# CHIP.net
KiCad netlist of a schematic drawn in Altium Designer
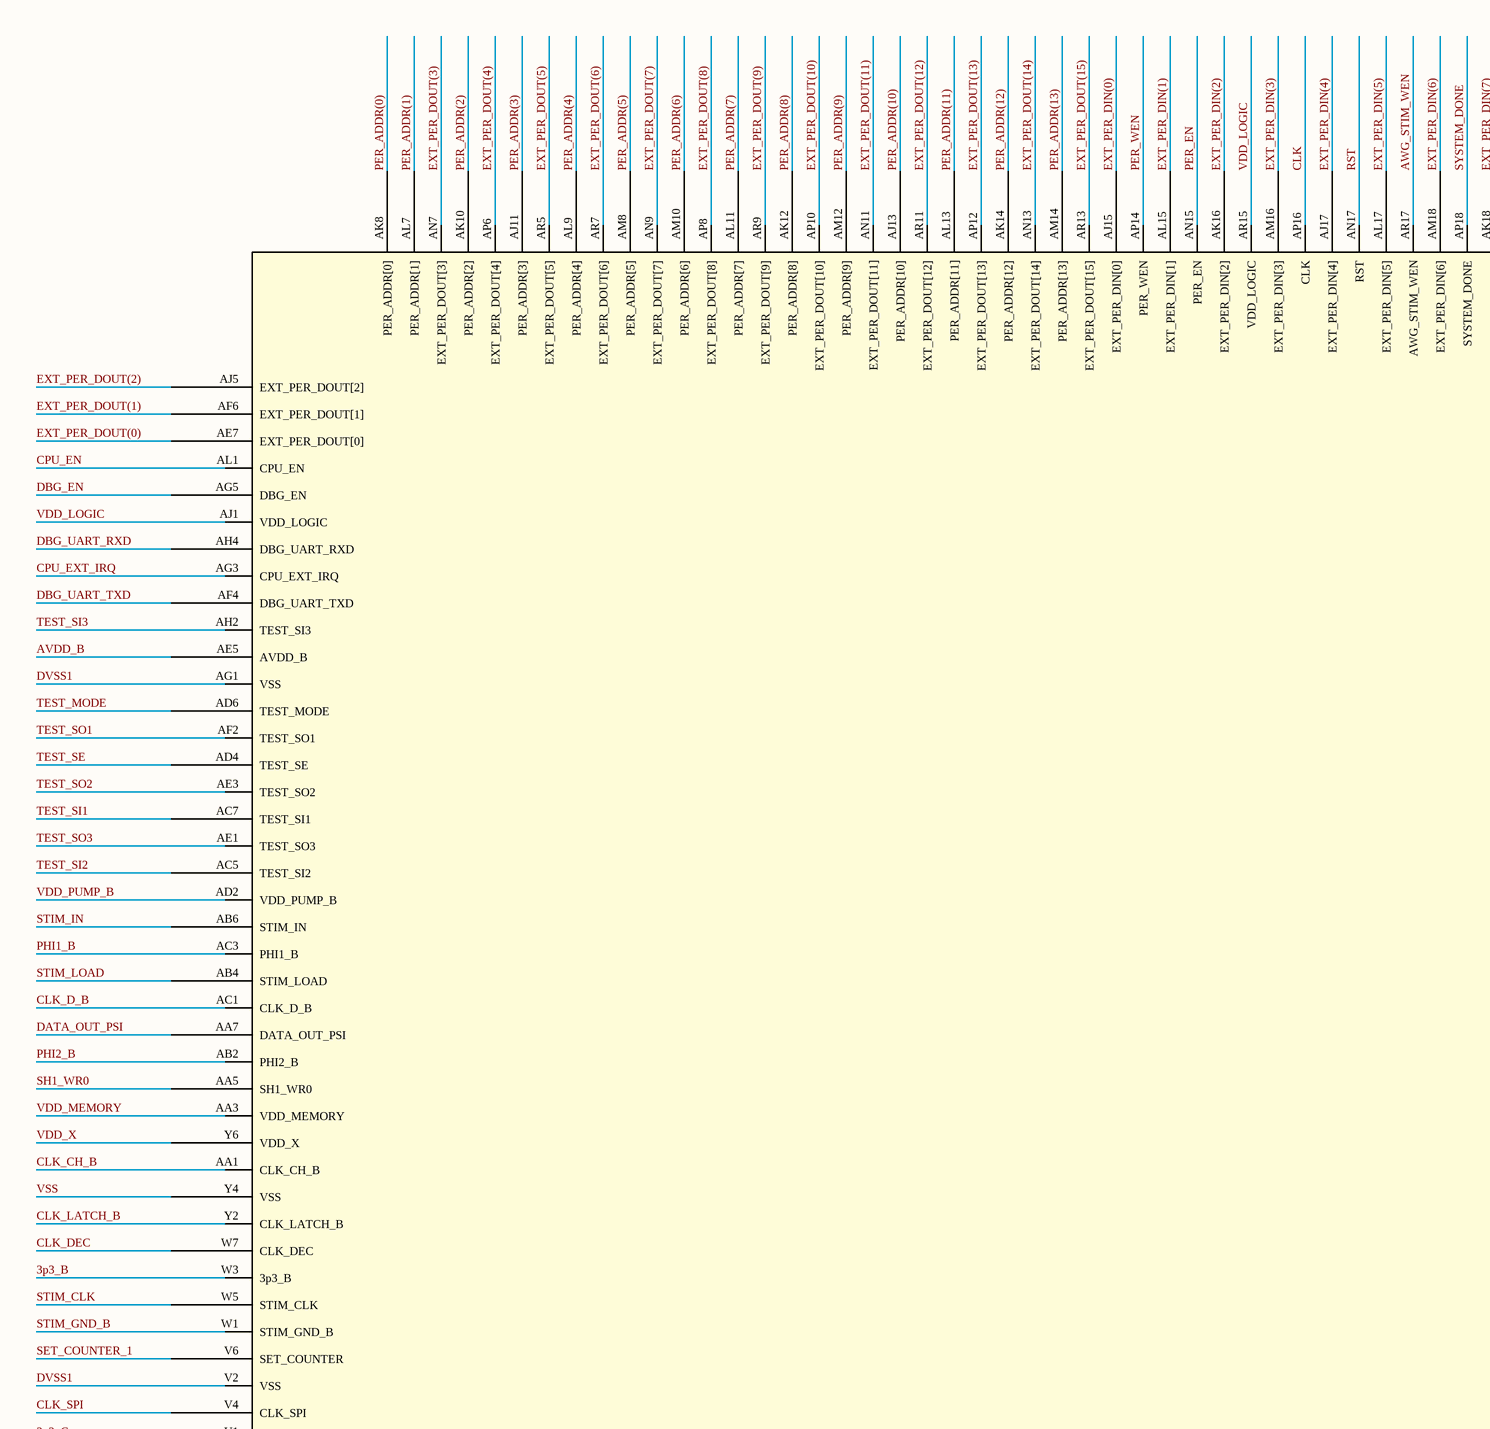
[diagram p0: CHIP.SchDoc, top left]
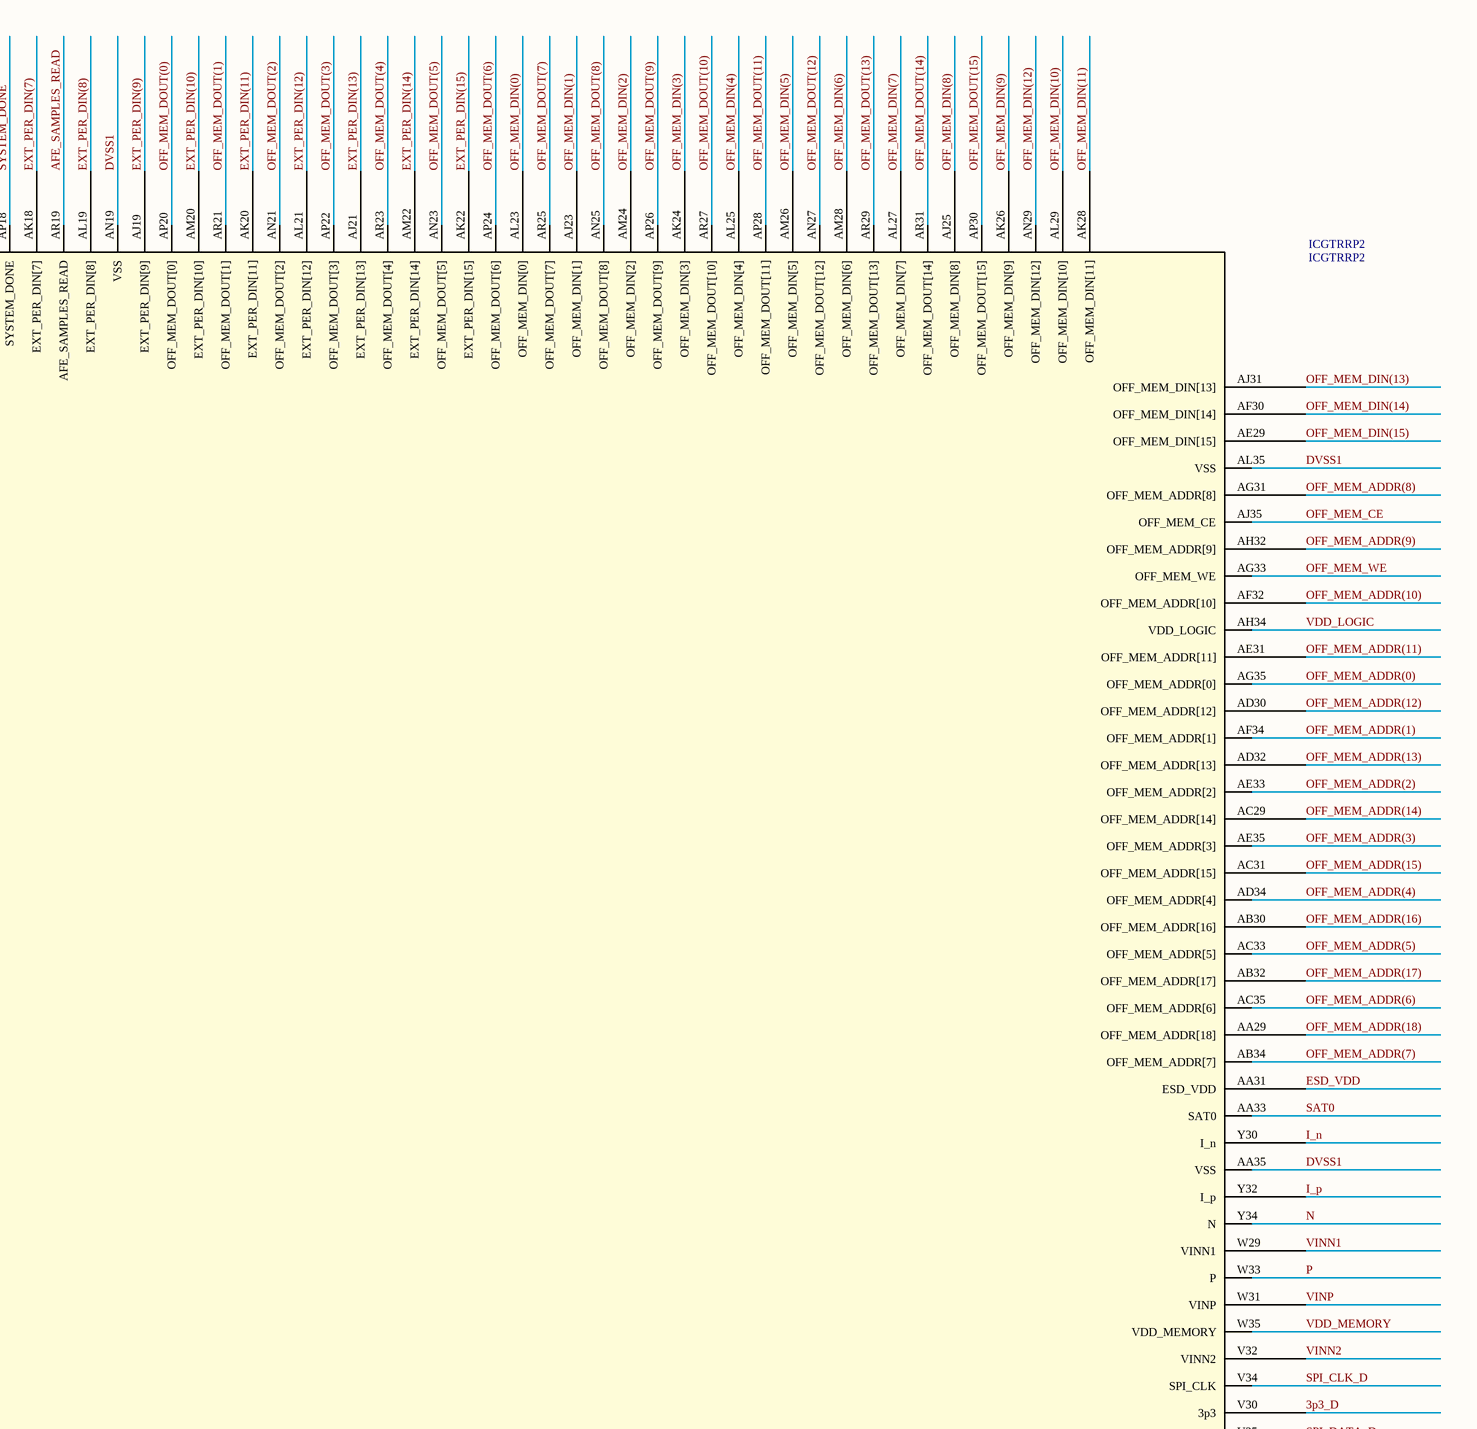
[diagram p1: CHIP.SchDoc, top right]
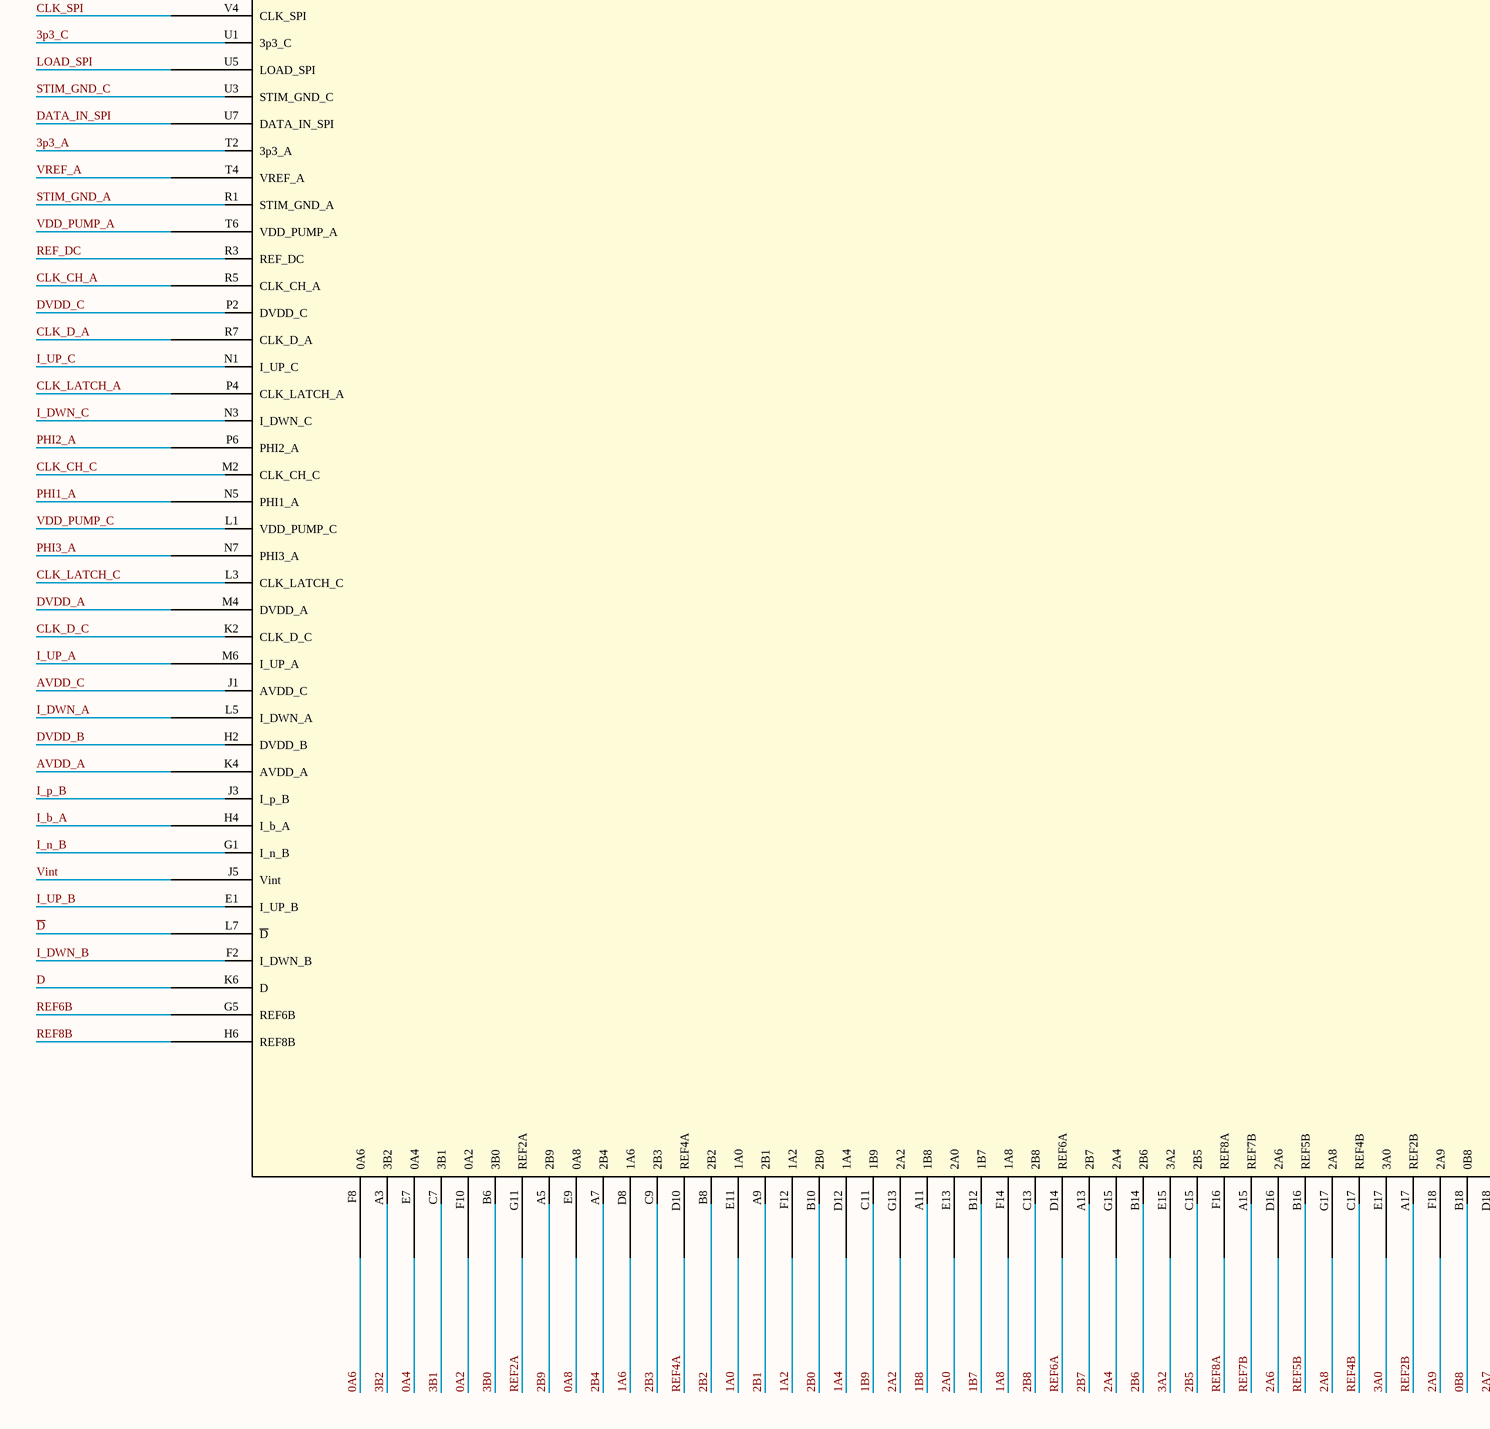
[diagram p2: CHIP.SchDoc, bottom left]
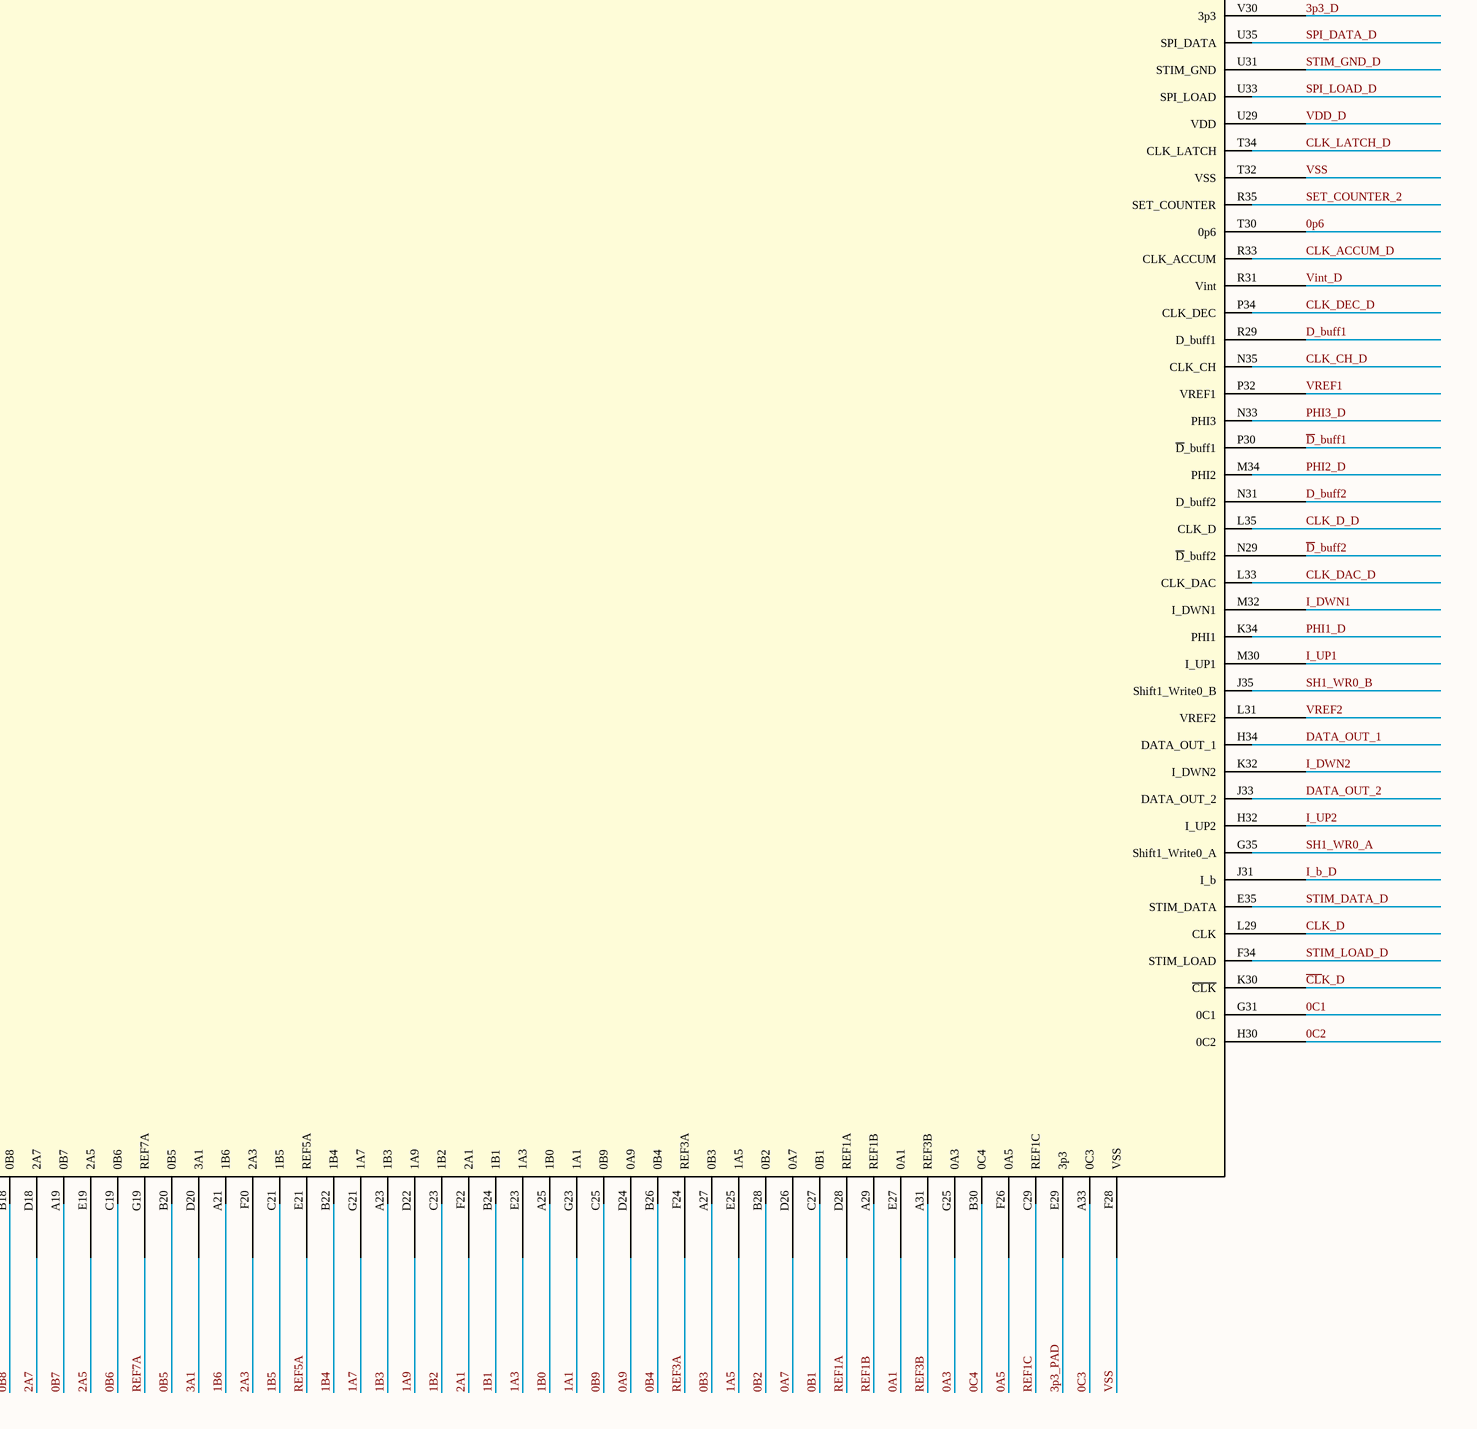
[diagram p3: CHIP.SchDoc, bottom right]

(export (version "E")
  (design (tool "Eeschema 10.0.6"))
  (components
    (comp (ref "ICGTRRP2")
      (value "ICGTRRP2")
      (footprint "PGA391")
      (libsource (lib "ICGTRRP2") (part "PGA391"))
    )
  )
  (nets
    (net (code "1") (name "/0A1") (class "Default")
      (node (ref "ICGTRRP2") (pin "E27") (pinfunction "0A1_E27") (pintype "passive"))
    )
    (net (code "2") (name "/0A2") (class "Default")
      (node (ref "ICGTRRP2") (pin "F10") (pinfunction "0A2_F10") (pintype "passive"))
    )
    (net (code "3") (name "/0A3") (class "Default")
      (node (ref "ICGTRRP2") (pin "G25") (pinfunction "0A3_G25") (pintype "passive"))
    )
    (net (code "4") (name "/0A4") (class "Default")
      (node (ref "ICGTRRP2") (pin "E7") (pinfunction "0A4_E7") (pintype "passive"))
    )
    (net (code "5") (name "/0A5") (class "Default")
      (node (ref "ICGTRRP2") (pin "F26") (pinfunction "0A5_F26") (pintype "passive"))
    )
    (net (code "6") (name "/0A6") (class "Default")
      (node (ref "ICGTRRP2") (pin "F8") (pinfunction "0A6_F8") (pintype "passive"))
    )
    (net (code "7") (name "/0A7") (class "Default")
      (node (ref "ICGTRRP2") (pin "D26") (pinfunction "0A7_D26") (pintype "passive"))
    )
    (net (code "8") (name "/0A8") (class "Default")
      (node (ref "ICGTRRP2") (pin "E9") (pinfunction "0A8_E9") (pintype "passive"))
    )
    (net (code "9") (name "/0A9") (class "Default")
      (node (ref "ICGTRRP2") (pin "D24") (pinfunction "0A9_D24") (pintype "passive"))
    )
    (net (code "10") (name "/0B1") (class "Default")
      (node (ref "ICGTRRP2") (pin "C27") (pinfunction "0B1_C27") (pintype "passive"))
    )
    (net (code "11") (name "/0B2") (class "Default")
      (node (ref "ICGTRRP2") (pin "B28") (pinfunction "0B2_B28") (pintype "passive"))
    )
    (net (code "12") (name "/0B3") (class "Default")
      (node (ref "ICGTRRP2") (pin "A27") (pinfunction "0B3_A27") (pintype "passive"))
    )
    (net (code "13") (name "/0B4") (class "Default")
      (node (ref "ICGTRRP2") (pin "B26") (pinfunction "0B4_B26") (pintype "passive"))
    )
    (net (code "14") (name "/0B5") (class "Default")
      (node (ref "ICGTRRP2") (pin "B20") (pinfunction "0B5_B20") (pintype "passive"))
    )
    (net (code "15") (name "/0B6") (class "Default")
      (node (ref "ICGTRRP2") (pin "C19") (pinfunction "0B6_C19") (pintype "passive"))
    )
    (net (code "16") (name "/0B7") (class "Default")
      (node (ref "ICGTRRP2") (pin "A19") (pinfunction "0B7_A19") (pintype "passive"))
    )
    (net (code "17") (name "/0B8") (class "Default")
      (node (ref "ICGTRRP2") (pin "B18") (pinfunction "0B8_B18") (pintype "passive"))
    )
    (net (code "18") (name "/0B9") (class "Default")
      (node (ref "ICGTRRP2") (pin "C25") (pinfunction "0B9_C25") (pintype "passive"))
    )
    (net (code "19") (name "/0C1") (class "Default")
      (node (ref "ICGTRRP2") (pin "G31") (pinfunction "0C1_G31") (pintype "passive"))
    )
    (net (code "20") (name "/0C2") (class "Default")
      (node (ref "ICGTRRP2") (pin "H30") (pinfunction "0C2_H30") (pintype "passive"))
    )
    (net (code "21") (name "/0C3") (class "Default")
      (node (ref "ICGTRRP2") (pin "A33") (pinfunction "0C3_A33") (pintype "passive"))
    )
    (net (code "22") (name "/0C4") (class "Default")
      (node (ref "ICGTRRP2") (pin "B30") (pinfunction "0C4_B30") (pintype "passive"))
    )
    (net (code "23") (name "/0p6") (class "Default")
      (node (ref "ICGTRRP2") (pin "T30") (pinfunction "0p6_T30") (pintype "passive"))
    )
    (net (code "24") (name "/1A0") (class "Default")
      (node (ref "ICGTRRP2") (pin "E11") (pinfunction "1A0_E11") (pintype "passive"))
    )
    (net (code "25") (name "/1A1") (class "Default")
      (node (ref "ICGTRRP2") (pin "G23") (pinfunction "1A1_G23") (pintype "passive"))
    )
    (net (code "26") (name "/1A2") (class "Default")
      (node (ref "ICGTRRP2") (pin "F12") (pinfunction "1A2_F12") (pintype "passive"))
    )
    (net (code "27") (name "/1A3") (class "Default")
      (node (ref "ICGTRRP2") (pin "E23") (pinfunction "1A3_E23") (pintype "passive"))
    )
    (net (code "28") (name "/1A4") (class "Default")
      (node (ref "ICGTRRP2") (pin "D12") (pinfunction "1A4_D12") (pintype "passive"))
    )
    (net (code "29") (name "/1A5") (class "Default")
      (node (ref "ICGTRRP2") (pin "E25") (pinfunction "1A5_E25") (pintype "passive"))
    )
    (net (code "30") (name "/1A6") (class "Default")
      (node (ref "ICGTRRP2") (pin "D8") (pinfunction "1A6_D8") (pintype "passive"))
    )
    (net (code "31") (name "/1A7") (class "Default")
      (node (ref "ICGTRRP2") (pin "G21") (pinfunction "1A7_G21") (pintype "passive"))
    )
    (net (code "32") (name "/1A8") (class "Default")
      (node (ref "ICGTRRP2") (pin "F14") (pinfunction "1A8_F14") (pintype "passive"))
    )
    (net (code "33") (name "/1A9") (class "Default")
      (node (ref "ICGTRRP2") (pin "D22") (pinfunction "1A9_D22") (pintype "passive"))
    )
    (net (code "34") (name "/1B0") (class "Default")
      (node (ref "ICGTRRP2") (pin "A25") (pinfunction "1B0_A25") (pintype "passive"))
    )
    (net (code "35") (name "/1B1") (class "Default")
      (node (ref "ICGTRRP2") (pin "B24") (pinfunction "1B1_B24") (pintype "passive"))
    )
    (net (code "36") (name "/1B2") (class "Default")
      (node (ref "ICGTRRP2") (pin "C23") (pinfunction "1B2_C23") (pintype "passive"))
    )
    (net (code "37") (name "/1B3") (class "Default")
      (node (ref "ICGTRRP2") (pin "A23") (pinfunction "1B3_A23") (pintype "passive"))
    )
    (net (code "38") (name "/1B4") (class "Default")
      (node (ref "ICGTRRP2") (pin "B22") (pinfunction "1B4_B22") (pintype "passive"))
    )
    (net (code "39") (name "/1B5") (class "Default")
      (node (ref "ICGTRRP2") (pin "C21") (pinfunction "1B5_C21") (pintype "passive"))
    )
    (net (code "40") (name "/1B6") (class "Default")
      (node (ref "ICGTRRP2") (pin "A21") (pinfunction "1B6_A21") (pintype "passive"))
    )
    (net (code "41") (name "/1B7") (class "Default")
      (node (ref "ICGTRRP2") (pin "B12") (pinfunction "1B7_B12") (pintype "passive"))
    )
    (net (code "42") (name "/1B8") (class "Default")
      (node (ref "ICGTRRP2") (pin "A11") (pinfunction "1B8_A11") (pintype "passive"))
    )
    (net (code "43") (name "/1B9") (class "Default")
      (node (ref "ICGTRRP2") (pin "C11") (pinfunction "1B9_C11") (pintype "passive"))
    )
    (net (code "44") (name "/2A0") (class "Default")
      (node (ref "ICGTRRP2") (pin "E13") (pinfunction "2A0_E13") (pintype "passive"))
    )
    (net (code "45") (name "/2A1") (class "Default")
      (node (ref "ICGTRRP2") (pin "F22") (pinfunction "2A1_F22") (pintype "passive"))
    )
    (net (code "46") (name "/2A2") (class "Default")
      (node (ref "ICGTRRP2") (pin "G13") (pinfunction "2A2_G13") (pintype "passive"))
    )
    (net (code "47") (name "/2A3") (class "Default")
      (node (ref "ICGTRRP2") (pin "F20") (pinfunction "2A3_F20") (pintype "passive"))
    )
    (net (code "48") (name "/2A4") (class "Default")
      (node (ref "ICGTRRP2") (pin "G15") (pinfunction "2A4_G15") (pintype "passive"))
    )
    (net (code "49") (name "/2A5") (class "Default")
      (node (ref "ICGTRRP2") (pin "E19") (pinfunction "2A5_E19") (pintype "passive"))
    )
    (net (code "50") (name "/2A6") (class "Default")
      (node (ref "ICGTRRP2") (pin "D16") (pinfunction "2A6_D16") (pintype "passive"))
    )
    (net (code "51") (name "/2A7") (class "Default")
      (node (ref "ICGTRRP2") (pin "D18") (pinfunction "2A7_D18") (pintype "passive"))
    )
    (net (code "52") (name "/2A8") (class "Default")
      (node (ref "ICGTRRP2") (pin "G17") (pinfunction "2A8_G17") (pintype "passive"))
    )
    (net (code "53") (name "/2A9") (class "Default")
      (node (ref "ICGTRRP2") (pin "F18") (pinfunction "2A9_F18") (pintype "passive"))
    )
    (net (code "54") (name "/2B0") (class "Default")
      (node (ref "ICGTRRP2") (pin "B10") (pinfunction "2B0_B10") (pintype "passive"))
    )
    (net (code "55") (name "/2B1") (class "Default")
      (node (ref "ICGTRRP2") (pin "A9") (pinfunction "2B1_A9") (pintype "passive"))
    )
    (net (code "56") (name "/2B2") (class "Default")
      (node (ref "ICGTRRP2") (pin "B8") (pinfunction "2B2_B8") (pintype "passive"))
    )
    (net (code "57") (name "/2B3") (class "Default")
      (node (ref "ICGTRRP2") (pin "C9") (pinfunction "2B3_C9") (pintype "passive"))
    )
    (net (code "58") (name "/2B4") (class "Default")
      (node (ref "ICGTRRP2") (pin "A7") (pinfunction "2B4_A7") (pintype "passive"))
    )
    (net (code "59") (name "/2B5") (class "Default")
      (node (ref "ICGTRRP2") (pin "C15") (pinfunction "2B5_C15") (pintype "passive"))
    )
    (net (code "60") (name "/2B6") (class "Default")
      (node (ref "ICGTRRP2") (pin "B14") (pinfunction "2B6_B14") (pintype "passive"))
    )
    (net (code "61") (name "/2B7") (class "Default")
      (node (ref "ICGTRRP2") (pin "A13") (pinfunction "2B7_A13") (pintype "passive"))
    )
    (net (code "62") (name "/2B8") (class "Default")
      (node (ref "ICGTRRP2") (pin "C13") (pinfunction "2B8_C13") (pintype "passive"))
    )
    (net (code "63") (name "/2B9") (class "Default")
      (node (ref "ICGTRRP2") (pin "A5") (pinfunction "2B9_A5") (pintype "passive"))
    )
    (net (code "64") (name "/3A0") (class "Default")
      (node (ref "ICGTRRP2") (pin "E17") (pinfunction "3A0_E17") (pintype "passive"))
    )
    (net (code "65") (name "/3A1") (class "Default")
      (node (ref "ICGTRRP2") (pin "D20") (pinfunction "3A1_D20") (pintype "passive"))
    )
    (net (code "66") (name "/3A2") (class "Default")
      (node (ref "ICGTRRP2") (pin "E15") (pinfunction "3A2_E15") (pintype "passive"))
    )
    (net (code "67") (name "/3B0") (class "Default")
      (node (ref "ICGTRRP2") (pin "B6") (pinfunction "3B0_B6") (pintype "passive"))
    )
    (net (code "68") (name "/3B1") (class "Default")
      (node (ref "ICGTRRP2") (pin "C7") (pinfunction "3B1_C7") (pintype "passive"))
    )
    (net (code "69") (name "/3B2") (class "Default")
      (node (ref "ICGTRRP2") (pin "A3") (pinfunction "3B2_A3") (pintype "passive"))
    )
    (net (code "70") (name "/3p3_A") (class "Default")
      (node (ref "ICGTRRP2") (pin "T2") (pinfunction "3p3_A_T2") (pintype "passive"))
    )
    (net (code "71") (name "/3p3_B") (class "Default")
      (node (ref "ICGTRRP2") (pin "W3") (pinfunction "3p3_B_W3") (pintype "passive"))
    )
    (net (code "72") (name "/3p3_C") (class "Default")
      (node (ref "ICGTRRP2") (pin "U1") (pinfunction "3p3_C_U1") (pintype "passive"))
    )
    (net (code "73") (name "/3p3_D") (class "Default")
      (node (ref "ICGTRRP2") (pin "V30") (pinfunction "3p3_V30") (pintype "passive"))
    )
    (net (code "74") (name "/3p3_PAD") (class "Default")
      (node (ref "ICGTRRP2") (pin "E29") (pinfunction "3p3_E29") (pintype "passive"))
    )
    (net (code "75") (name "/AFE_SAMPLES_READ") (class "Default")
      (node (ref "ICGTRRP2") (pin "AR19") (pinfunction "AFE_SAMPLES_READ_AR19") (pintype "passive"))
    )
    (net (code "76") (name "/AVDD_A") (class "Default")
      (node (ref "ICGTRRP2") (pin "K4") (pinfunction "AVDD_A_K4") (pintype "passive"))
    )
    (net (code "77") (name "/AVDD_B") (class "Default")
      (node (ref "ICGTRRP2") (pin "AE5") (pinfunction "AVDD_B_AE5") (pintype "passive"))
    )
    (net (code "78") (name "/AVDD_C") (class "Default")
      (node (ref "ICGTRRP2") (pin "J1") (pinfunction "AVDD_C_J1") (pintype "passive"))
    )
    (net (code "79") (name "/AWG_STIM_WEN") (class "Default")
      (node (ref "ICGTRRP2") (pin "AR17") (pinfunction "AWG_STIM_WEN_AR17") (pintype "passive"))
    )
    (net (code "80") (name "/CLK") (class "Default")
      (node (ref "ICGTRRP2") (pin "AP16") (pinfunction "CLK_AP16") (pintype "passive"))
    )
    (net (code "81") (name "/CLK_ACCUM_D") (class "Default")
      (node (ref "ICGTRRP2") (pin "R33") (pinfunction "CLK_ACCUM_R33") (pintype "passive"))
    )
    (net (code "82") (name "/CLK_CH_A") (class "Default")
      (node (ref "ICGTRRP2") (pin "R5") (pinfunction "CLK_CH_A_R5") (pintype "passive"))
    )
    (net (code "83") (name "/CLK_CH_B") (class "Default")
      (node (ref "ICGTRRP2") (pin "AA1") (pinfunction "CLK_CH_B_AA1") (pintype "passive"))
    )
    (net (code "84") (name "/CLK_CH_C") (class "Default")
      (node (ref "ICGTRRP2") (pin "M2") (pinfunction "CLK_CH_C_M2") (pintype "passive"))
    )
    (net (code "85") (name "/CLK_CH_D") (class "Default")
      (node (ref "ICGTRRP2") (pin "N35") (pinfunction "CLK_CH_N35") (pintype "passive"))
    )
    (net (code "86") (name "/CLK_D") (class "Default")
      (node (ref "ICGTRRP2") (pin "L29") (pinfunction "CLK_L29") (pintype "passive"))
    )
    (net (code "87") (name "/CLK_DAC_D") (class "Default")
      (node (ref "ICGTRRP2") (pin "L33") (pinfunction "CLK_DAC_L33") (pintype "passive"))
    )
    (net (code "88") (name "/CLK_DEC") (class "Default")
      (node (ref "ICGTRRP2") (pin "W7") (pinfunction "CLK_DEC_W7") (pintype "passive"))
    )
    (net (code "89") (name "/CLK_DEC_D") (class "Default")
      (node (ref "ICGTRRP2") (pin "P34") (pinfunction "CLK_DEC_P34") (pintype "passive"))
    )
    (net (code "90") (name "/CLK_D_A") (class "Default")
      (node (ref "ICGTRRP2") (pin "R7") (pinfunction "CLK_D_A_R7") (pintype "passive"))
    )
    (net (code "91") (name "/CLK_D_B") (class "Default")
      (node (ref "ICGTRRP2") (pin "AC1") (pinfunction "CLK_D_B_AC1") (pintype "passive"))
    )
    (net (code "92") (name "/CLK_D_C") (class "Default")
      (node (ref "ICGTRRP2") (pin "K2") (pinfunction "CLK_D_C_K2") (pintype "passive"))
    )
    (net (code "93") (name "/CLK_D_D") (class "Default")
      (node (ref "ICGTRRP2") (pin "L35") (pinfunction "CLK_D_L35") (pintype "passive"))
    )
    (net (code "94") (name "/CLK_LATCH_A") (class "Default")
      (node (ref "ICGTRRP2") (pin "P4") (pinfunction "CLK_LATCH_A_P4") (pintype "passive"))
    )
    (net (code "95") (name "/CLK_LATCH_B") (class "Default")
      (node (ref "ICGTRRP2") (pin "Y2") (pinfunction "CLK_LATCH_B_Y2") (pintype "passive"))
    )
    (net (code "96") (name "/CLK_LATCH_C") (class "Default")
      (node (ref "ICGTRRP2") (pin "L3") (pinfunction "CLK_LATCH_C_L3") (pintype "passive"))
    )
    (net (code "97") (name "/CLK_LATCH_D") (class "Default")
      (node (ref "ICGTRRP2") (pin "T34") (pinfunction "CLK_LATCH_T34") (pintype "passive"))
    )
    (net (code "98") (name "/CLK_SPI") (class "Default")
      (node (ref "ICGTRRP2") (pin "V4") (pinfunction "CLK_SPI_V4") (pintype "passive"))
    )
    (net (code "99") (name "/CPU_EN") (class "Default")
      (node (ref "ICGTRRP2") (pin "AL1") (pinfunction "CPU_EN_AL1") (pintype "passive"))
    )
    (net (code "100") (name "/CPU_EXT_IRQ") (class "Default")
      (node (ref "ICGTRRP2") (pin "AG3") (pinfunction "CPU_EXT_IRQ_AG3") (pintype "passive"))
    )
    (net (code "101") (name "/D") (class "Default")
      (node (ref "ICGTRRP2") (pin "K6") (pinfunction "D_K6") (pintype "passive"))
    )
    (net (code "102") (name "/DATA_IN_SPI") (class "Default")
      (node (ref "ICGTRRP2") (pin "U7") (pinfunction "DATA_IN_SPI_U7") (pintype "passive"))
    )
    (net (code "103") (name "/DATA_OUT_1") (class "Default")
      (node (ref "ICGTRRP2") (pin "H34") (pinfunction "DATA_OUT_1_H34") (pintype "passive"))
    )
    (net (code "104") (name "/DATA_OUT_2") (class "Default")
      (node (ref "ICGTRRP2") (pin "J33") (pinfunction "DATA_OUT_2_J33") (pintype "passive"))
    )
    (net (code "105") (name "/DATA_OUT_PSI") (class "Default")
      (node (ref "ICGTRRP2") (pin "AA7") (pinfunction "DATA_OUT_PSI_AA7") (pintype "passive"))
    )
    (net (code "106") (name "/DBG_EN") (class "Default")
      (node (ref "ICGTRRP2") (pin "AG5") (pinfunction "DBG_EN_AG5") (pintype "passive"))
    )
    (net (code "107") (name "/DBG_UART_RXD") (class "Default")
      (node (ref "ICGTRRP2") (pin "AH4") (pinfunction "DBG_UART_RXD_AH4") (pintype "passive"))
    )
    (net (code "108") (name "/DBG_UART_TXD") (class "Default")
      (node (ref "ICGTRRP2") (pin "AF4") (pinfunction "DBG_UART_TXD_AF4") (pintype "passive"))
    )
    (net (code "109") (name "/DVDD_A") (class "Default")
      (node (ref "ICGTRRP2") (pin "M4") (pinfunction "DVDD_A_M4") (pintype "passive"))
    )
    (net (code "110") (name "/DVDD_B") (class "Default")
      (node (ref "ICGTRRP2") (pin "H2") (pinfunction "DVDD_B_H2") (pintype "passive"))
    )
    (net (code "111") (name "/DVDD_C") (class "Default")
      (node (ref "ICGTRRP2") (pin "P2") (pinfunction "DVDD_C_P2") (pintype "passive"))
    )
    (net (code "112") (name "/DVSS1") (class "Default")
      (node (ref "ICGTRRP2") (pin "AA35") (pinfunction "VSS_AA35") (pintype "passive"))
      (node (ref "ICGTRRP2") (pin "AG1") (pinfunction "VSS_AG1") (pintype "passive"))
      (node (ref "ICGTRRP2") (pin "AL35") (pinfunction "VSS_AL35") (pintype "passive"))
      (node (ref "ICGTRRP2") (pin "AN19") (pinfunction "VSS_AN19") (pintype "passive"))
      (node (ref "ICGTRRP2") (pin "V2") (pinfunction "VSS_V2") (pintype "passive"))
    )
    (net (code "113") (name "/D_buff1") (class "Default")
      (node (ref "ICGTRRP2") (pin "R29") (pinfunction "D_buff1_R29") (pintype "passive"))
    )
    (net (code "114") (name "/D_buff2") (class "Default")
      (node (ref "ICGTRRP2") (pin "N31") (pinfunction "D_buff2_N31") (pintype "passive"))
    )
    (net (code "115") (name "/ESD_VDD") (class "Default")
      (node (ref "ICGTRRP2") (pin "AA31") (pinfunction "ESD_VDD_AA31") (pintype "passive"))
    )
    (net (code "116") (name "/EXT_PER_DIN(0)") (class "Default")
      (node (ref "ICGTRRP2") (pin "AJ15") (pinfunction "EXT_PER_DIN[0]_AJ15") (pintype "passive"))
    )
    (net (code "117") (name "/EXT_PER_DIN(1)") (class "Default")
      (node (ref "ICGTRRP2") (pin "AL15") (pinfunction "EXT_PER_DIN[1]_AL15") (pintype "passive"))
    )
    (net (code "118") (name "/EXT_PER_DIN(2)") (class "Default")
      (node (ref "ICGTRRP2") (pin "AK16") (pinfunction "EXT_PER_DIN[2]_AK16") (pintype "passive"))
    )
    (net (code "119") (name "/EXT_PER_DIN(3)") (class "Default")
      (node (ref "ICGTRRP2") (pin "AM16") (pinfunction "EXT_PER_DIN[3]_AM16") (pintype "passive"))
    )
    (net (code "120") (name "/EXT_PER_DIN(4)") (class "Default")
      (node (ref "ICGTRRP2") (pin "AJ17") (pinfunction "EXT_PER_DIN[4]_AJ17") (pintype "passive"))
    )
    (net (code "121") (name "/EXT_PER_DIN(5)") (class "Default")
      (node (ref "ICGTRRP2") (pin "AL17") (pinfunction "EXT_PER_DIN[5]_AL17") (pintype "passive"))
    )
    (net (code "122") (name "/EXT_PER_DIN(6)") (class "Default")
      (node (ref "ICGTRRP2") (pin "AM18") (pinfunction "EXT_PER_DIN[6]_AM18") (pintype "passive"))
    )
    (net (code "123") (name "/EXT_PER_DIN(7)") (class "Default")
      (node (ref "ICGTRRP2") (pin "AK18") (pinfunction "EXT_PER_DIN[7]_AK18") (pintype "passive"))
    )
    (net (code "124") (name "/EXT_PER_DIN(8)") (class "Default")
      (node (ref "ICGTRRP2") (pin "AL19") (pinfunction "EXT_PER_DIN[8]_AL19") (pintype "passive"))
    )
    (net (code "125") (name "/EXT_PER_DIN(9)") (class "Default")
      (node (ref "ICGTRRP2") (pin "AJ19") (pinfunction "EXT_PER_DIN[9]_AJ19") (pintype "passive"))
    )
    (net (code "126") (name "/EXT_PER_DIN(10)") (class "Default")
      (node (ref "ICGTRRP2") (pin "AM20") (pinfunction "EXT_PER_DIN[10]_AM20") (pintype "passive"))
    )
    (net (code "127") (name "/EXT_PER_DIN(11)") (class "Default")
      (node (ref "ICGTRRP2") (pin "AK20") (pinfunction "EXT_PER_DIN[11]_AK20") (pintype "passive"))
    )
    (net (code "128") (name "/EXT_PER_DIN(12)") (class "Default")
      (node (ref "ICGTRRP2") (pin "AL21") (pinfunction "EXT_PER_DIN[12]_AL21") (pintype "passive"))
    )
    (net (code "129") (name "/EXT_PER_DIN(13)") (class "Default")
      (node (ref "ICGTRRP2") (pin "AJ21") (pinfunction "EXT_PER_DIN[13]_AJ21") (pintype "passive"))
    )
    (net (code "130") (name "/EXT_PER_DIN(14)") (class "Default")
      (node (ref "ICGTRRP2") (pin "AM22") (pinfunction "EXT_PER_DIN[14]_AM22") (pintype "passive"))
    )
    (net (code "131") (name "/EXT_PER_DIN(15)") (class "Default")
      (node (ref "ICGTRRP2") (pin "AK22") (pinfunction "EXT_PER_DIN[15]_AK22") (pintype "passive"))
    )
    (net (code "132") (name "/EXT_PER_DOUT(0)") (class "Default")
      (node (ref "ICGTRRP2") (pin "AE7") (pinfunction "EXT_PER_DOUT[0]_AE7") (pintype "passive"))
    )
    (net (code "133") (name "/EXT_PER_DOUT(1)") (class "Default")
      (node (ref "ICGTRRP2") (pin "AF6") (pinfunction "EXT_PER_DOUT[1]_AF6") (pintype "passive"))
    )
    (net (code "134") (name "/EXT_PER_DOUT(2)") (class "Default")
      (node (ref "ICGTRRP2") (pin "AJ5") (pinfunction "EXT_PER_DOUT[2]_AJ5") (pintype "passive"))
    )
    (net (code "135") (name "/EXT_PER_DOUT(3)") (class "Default")
      (node (ref "ICGTRRP2") (pin "AN7") (pinfunction "EXT_PER_DOUT[3]_AN7") (pintype "passive"))
    )
    (net (code "136") (name "/EXT_PER_DOUT(4)") (class "Default")
      (node (ref "ICGTRRP2") (pin "AP6") (pinfunction "EXT_PER_DOUT[4]_AP6") (pintype "passive"))
    )
    (net (code "137") (name "/EXT_PER_DOUT(5)") (class "Default")
      (node (ref "ICGTRRP2") (pin "AR5") (pinfunction "EXT_PER_DOUT[5]_AR5") (pintype "passive"))
    )
    (net (code "138") (name "/EXT_PER_DOUT(6)") (class "Default")
      (node (ref "ICGTRRP2") (pin "AR7") (pinfunction "EXT_PER_DOUT[6]_AR7") (pintype "passive"))
    )
    (net (code "139") (name "/EXT_PER_DOUT(7)") (class "Default")
      (node (ref "ICGTRRP2") (pin "AN9") (pinfunction "EXT_PER_DOUT[7]_AN9") (pintype "passive"))
    )
    (net (code "140") (name "/EXT_PER_DOUT(8)") (class "Default")
      (node (ref "ICGTRRP2") (pin "AP8") (pinfunction "EXT_PER_DOUT[8]_AP8") (pintype "passive"))
    )
    (net (code "141") (name "/EXT_PER_DOUT(9)") (class "Default")
      (node (ref "ICGTRRP2") (pin "AR9") (pinfunction "EXT_PER_DOUT[9]_AR9") (pintype "passive"))
    )
    (net (code "142") (name "/EXT_PER_DOUT(10)") (class "Default")
      (node (ref "ICGTRRP2") (pin "AP10") (pinfunction "EXT_PER_DOUT[10]_AP10") (pintype "passive"))
    )
    (net (code "143") (name "/EXT_PER_DOUT(11)") (class "Default")
      (node (ref "ICGTRRP2") (pin "AN11") (pinfunction "EXT_PER_DOUT[11]_AN11") (pintype "passive"))
    )
    (net (code "144") (name "/EXT_PER_DOUT(12)") (class "Default")
      (node (ref "ICGTRRP2") (pin "AR11") (pinfunction "EXT_PER_DOUT[12]_AR11") (pintype "passive"))
    )
    (net (code "145") (name "/EXT_PER_DOUT(13)") (class "Default")
      (node (ref "ICGTRRP2") (pin "AP12") (pinfunction "EXT_PER_DOUT[13]_AP12") (pintype "passive"))
    )
    (net (code "146") (name "/EXT_PER_DOUT(14)") (class "Default")
      (node (ref "ICGTRRP2") (pin "AN13") (pinfunction "EXT_PER_DOUT[14]_AN13") (pintype "passive"))
    )
    (net (code "147") (name "/EXT_PER_DOUT(15)") (class "Default")
      (node (ref "ICGTRRP2") (pin "AR13") (pinfunction "EXT_PER_DOUT[15]_AR13") (pintype "passive"))
    )
    (net (code "148") (name "/I_DWN1") (class "Default")
      (node (ref "ICGTRRP2") (pin "M32") (pinfunction "I_DWN1_M32") (pintype "passive"))
    )
    (net (code "149") (name "/I_DWN2") (class "Default")
      (node (ref "ICGTRRP2") (pin "K32") (pinfunction "I_DWN2_K32") (pintype "passive"))
    )
    (net (code "150") (name "/I_DWN_A") (class "Default")
      (node (ref "ICGTRRP2") (pin "L5") (pinfunction "I_DWN_A_L5") (pintype "passive"))
    )
    (net (code "151") (name "/I_DWN_B") (class "Default")
      (node (ref "ICGTRRP2") (pin "F2") (pinfunction "I_DWN_B_F2") (pintype "passive"))
    )
    (net (code "152") (name "/I_DWN_C") (class "Default")
      (node (ref "ICGTRRP2") (pin "N3") (pinfunction "I_DWN_C_N3") (pintype "passive"))
    )
    (net (code "153") (name "/I_UP1") (class "Default")
      (node (ref "ICGTRRP2") (pin "M30") (pinfunction "I_UP1_M30") (pintype "passive"))
    )
    (net (code "154") (name "/I_UP2") (class "Default")
      (node (ref "ICGTRRP2") (pin "H32") (pinfunction "I_UP2_H32") (pintype "passive"))
    )
    (net (code "155") (name "/I_UP_A") (class "Default")
      (node (ref "ICGTRRP2") (pin "M6") (pinfunction "I_UP_A_M6") (pintype "passive"))
    )
    (net (code "156") (name "/I_UP_B") (class "Default")
      (node (ref "ICGTRRP2") (pin "E1") (pinfunction "I_UP_B_E1") (pintype "passive"))
    )
    (net (code "157") (name "/I_UP_C") (class "Default")
      (node (ref "ICGTRRP2") (pin "N1") (pinfunction "I_UP_C_N1") (pintype "passive"))
    )
    (net (code "158") (name "/I_b_A") (class "Default")
      (node (ref "ICGTRRP2") (pin "H4") (pinfunction "I_b_A_H4") (pintype "passive"))
    )
    (net (code "159") (name "/I_b_D") (class "Default")
      (node (ref "ICGTRRP2") (pin "J31") (pinfunction "I_b_J31") (pintype "passive"))
    )
    (net (code "160") (name "/I_n") (class "Default")
      (node (ref "ICGTRRP2") (pin "Y30") (pinfunction "I_n_Y30") (pintype "passive"))
    )
    (net (code "161") (name "/I_n_B") (class "Default")
      (node (ref "ICGTRRP2") (pin "G1") (pinfunction "I_n_B_G1") (pintype "passive"))
    )
    (net (code "162") (name "/I_p") (class "Default")
      (node (ref "ICGTRRP2") (pin "Y32") (pinfunction "I_p_Y32") (pintype "passive"))
    )
    (net (code "163") (name "/I_p_B") (class "Default")
      (node (ref "ICGTRRP2") (pin "J3") (pinfunction "I_p_B_J3") (pintype "passive"))
    )
    (net (code "164") (name "/LOAD_SPI") (class "Default")
      (node (ref "ICGTRRP2") (pin "U5") (pinfunction "LOAD_SPI_U5") (pintype "passive"))
    )
    (net (code "165") (name "/N") (class "Default")
      (node (ref "ICGTRRP2") (pin "Y34") (pinfunction "N_Y34") (pintype "passive"))
    )
    (net (code "166") (name "/OFF_MEM_ADDR(0)") (class "Default")
      (node (ref "ICGTRRP2") (pin "AG35") (pinfunction "OFF_MEM_ADDR[0]_AG35") (pintype "passive"))
    )
    (net (code "167") (name "/OFF_MEM_ADDR(1)") (class "Default")
      (node (ref "ICGTRRP2") (pin "AF34") (pinfunction "OFF_MEM_ADDR[1]_AF34") (pintype "passive"))
    )
    (net (code "168") (name "/OFF_MEM_ADDR(2)") (class "Default")
      (node (ref "ICGTRRP2") (pin "AE33") (pinfunction "OFF_MEM_ADDR[2]_AE33") (pintype "passive"))
    )
    (net (code "169") (name "/OFF_MEM_ADDR(3)") (class "Default")
      (node (ref "ICGTRRP2") (pin "AE35") (pinfunction "OFF_MEM_ADDR[3]_AE35") (pintype "passive"))
    )
    (net (code "170") (name "/OFF_MEM_ADDR(4)") (class "Default")
      (node (ref "ICGTRRP2") (pin "AD34") (pinfunction "OFF_MEM_ADDR[4]_AD34") (pintype "passive"))
    )
    (net (code "171") (name "/OFF_MEM_ADDR(5)") (class "Default")
      (node (ref "ICGTRRP2") (pin "AC33") (pinfunction "OFF_MEM_ADDR[5]_AC33") (pintype "passive"))
    )
    (net (code "172") (name "/OFF_MEM_ADDR(6)") (class "Default")
      (node (ref "ICGTRRP2") (pin "AC35") (pinfunction "OFF_MEM_ADDR[6]_AC35") (pintype "passive"))
    )
    (net (code "173") (name "/OFF_MEM_ADDR(7)") (class "Default")
      (node (ref "ICGTRRP2") (pin "AB34") (pinfunction "OFF_MEM_ADDR[7]_AB34") (pintype "passive"))
    )
    (net (code "174") (name "/OFF_MEM_ADDR(8)") (class "Default")
      (node (ref "ICGTRRP2") (pin "AG31") (pinfunction "OFF_MEM_ADDR[8]_AG31") (pintype "passive"))
    )
    (net (code "175") (name "/OFF_MEM_ADDR(9)") (class "Default")
      (node (ref "ICGTRRP2") (pin "AH32") (pinfunction "OFF_MEM_ADDR[9]_AH32") (pintype "passive"))
    )
    (net (code "176") (name "/OFF_MEM_ADDR(10)") (class "Default")
      (node (ref "ICGTRRP2") (pin "AF32") (pinfunction "OFF_MEM_ADDR[10]_AF32") (pintype "passive"))
    )
    (net (code "177") (name "/OFF_MEM_ADDR(11)") (class "Default")
      (node (ref "ICGTRRP2") (pin "AE31") (pinfunction "OFF_MEM_ADDR[11]_AE31") (pintype "passive"))
    )
    (net (code "178") (name "/OFF_MEM_ADDR(12)") (class "Default")
      (node (ref "ICGTRRP2") (pin "AD30") (pinfunction "OFF_MEM_ADDR[12]_AD30") (pintype "passive"))
    )
    (net (code "179") (name "/OFF_MEM_ADDR(13)") (class "Default")
      (node (ref "ICGTRRP2") (pin "AD32") (pinfunction "OFF_MEM_ADDR[13]_AD32") (pintype "passive"))
    )
    (net (code "180") (name "/OFF_MEM_ADDR(14)") (class "Default")
      (node (ref "ICGTRRP2") (pin "AC29") (pinfunction "OFF_MEM_ADDR[14]_AC29") (pintype "passive"))
    )
    (net (code "181") (name "/OFF_MEM_ADDR(15)") (class "Default")
      (node (ref "ICGTRRP2") (pin "AC31") (pinfunction "OFF_MEM_ADDR[15]_AC31") (pintype "passive"))
    )
    (net (code "182") (name "/OFF_MEM_ADDR(16)") (class "Default")
      (node (ref "ICGTRRP2") (pin "AB30") (pinfunction "OFF_MEM_ADDR[16]_AB30") (pintype "passive"))
    )
    (net (code "183") (name "/OFF_MEM_ADDR(17)") (class "Default")
      (node (ref "ICGTRRP2") (pin "AB32") (pinfunction "OFF_MEM_ADDR[17]_AB32") (pintype "passive"))
    )
    (net (code "184") (name "/OFF_MEM_ADDR(18)") (class "Default")
      (node (ref "ICGTRRP2") (pin "AA29") (pinfunction "OFF_MEM_ADDR[18]_AA29") (pintype "passive"))
    )
    (net (code "185") (name "/OFF_MEM_CE") (class "Default")
      (node (ref "ICGTRRP2") (pin "AJ35") (pinfunction "OFF_MEM_CE_AJ35") (pintype "passive"))
    )
    (net (code "186") (name "/OFF_MEM_DIN(0)") (class "Default")
      (node (ref "ICGTRRP2") (pin "AL23") (pinfunction "OFF_MEM_DIN[0]_AL23") (pintype "passive"))
    )
    (net (code "187") (name "/OFF_MEM_DIN(1)") (class "Default")
      (node (ref "ICGTRRP2") (pin "AJ23") (pinfunction "OFF_MEM_DIN[1]_AJ23") (pintype "passive"))
    )
    (net (code "188") (name "/OFF_MEM_DIN(2)") (class "Default")
      (node (ref "ICGTRRP2") (pin "AM24") (pinfunction "OFF_MEM_DIN[2]_AM24") (pintype "passive"))
    )
    (net (code "189") (name "/OFF_MEM_DIN(3)") (class "Default")
      (node (ref "ICGTRRP2") (pin "AK24") (pinfunction "OFF_MEM_DIN[3]_AK24") (pintype "passive"))
    )
    (net (code "190") (name "/OFF_MEM_DIN(4)") (class "Default")
      (node (ref "ICGTRRP2") (pin "AL25") (pinfunction "OFF_MEM_DIN[4]_AL25") (pintype "passive"))
    )
    (net (code "191") (name "/OFF_MEM_DIN(5)") (class "Default")
      (node (ref "ICGTRRP2") (pin "AM26") (pinfunction "OFF_MEM_DIN[5]_AM26") (pintype "passive"))
    )
    (net (code "192") (name "/OFF_MEM_DIN(6)") (class "Default")
      (node (ref "ICGTRRP2") (pin "AM28") (pinfunction "OFF_MEM_DIN[6]_AM28") (pintype "passive"))
    )
    (net (code "193") (name "/OFF_MEM_DIN(7)") (class "Default")
      (node (ref "ICGTRRP2") (pin "AL27") (pinfunction "OFF_MEM_DIN[7]_AL27") (pintype "passive"))
    )
    (net (code "194") (name "/OFF_MEM_DIN(8)") (class "Default")
      (node (ref "ICGTRRP2") (pin "AJ25") (pinfunction "OFF_MEM_DIN[8]_AJ25") (pintype "passive"))
    )
    (net (code "195") (name "/OFF_MEM_DIN(9)") (class "Default")
      (node (ref "ICGTRRP2") (pin "AK26") (pinfunction "OFF_MEM_DIN[9]_AK26") (pintype "passive"))
    )
    (net (code "196") (name "/OFF_MEM_DIN(10)") (class "Default")
      (node (ref "ICGTRRP2") (pin "AL29") (pinfunction "OFF_MEM_DIN[10]_AL29") (pintype "passive"))
    )
    (net (code "197") (name "/OFF_MEM_DIN(11)") (class "Default")
      (node (ref "ICGTRRP2") (pin "AK28") (pinfunction "OFF_MEM_DIN[11]_AK28") (pintype "passive"))
    )
    (net (code "198") (name "/OFF_MEM_DIN(12)") (class "Default")
      (node (ref "ICGTRRP2") (pin "AN29") (pinfunction "OFF_MEM_DIN[12]_AN29") (pintype "passive"))
    )
    (net (code "199") (name "/OFF_MEM_DIN(13)") (class "Default")
      (node (ref "ICGTRRP2") (pin "AJ31") (pinfunction "OFF_MEM_DIN[13]_AJ31") (pintype "passive"))
    )
    (net (code "200") (name "/OFF_MEM_DIN(14)") (class "Default")
      (node (ref "ICGTRRP2") (pin "AF30") (pinfunction "OFF_MEM_DIN[14]_AF30") (pintype "passive"))
    )
    (net (code "201") (name "/OFF_MEM_DIN(15)") (class "Default")
      (node (ref "ICGTRRP2") (pin "AE29") (pinfunction "OFF_MEM_DIN[15]_AE29") (pintype "passive"))
    )
    (net (code "202") (name "/OFF_MEM_DOUT(0)") (class "Default")
      (node (ref "ICGTRRP2") (pin "AP20") (pinfunction "OFF_MEM_DOUT[0]_AP20") (pintype "passive"))
    )
    (net (code "203") (name "/OFF_MEM_DOUT(1)") (class "Default")
      (node (ref "ICGTRRP2") (pin "AR21") (pinfunction "OFF_MEM_DOUT[1]_AR21") (pintype "passive"))
    )
    (net (code "204") (name "/OFF_MEM_DOUT(2)") (class "Default")
      (node (ref "ICGTRRP2") (pin "AN21") (pinfunction "OFF_MEM_DOUT[2]_AN21") (pintype "passive"))
    )
    (net (code "205") (name "/OFF_MEM_DOUT(3)") (class "Default")
      (node (ref "ICGTRRP2") (pin "AP22") (pinfunction "OFF_MEM_DOUT[3]_AP22") (pintype "passive"))
    )
    (net (code "206") (name "/OFF_MEM_DOUT(4)") (class "Default")
      (node (ref "ICGTRRP2") (pin "AR23") (pinfunction "OFF_MEM_DOUT[4]_AR23") (pintype "passive"))
    )
    (net (code "207") (name "/OFF_MEM_DOUT(5)") (class "Default")
      (node (ref "ICGTRRP2") (pin "AN23") (pinfunction "OFF_MEM_DOUT[5]_AN23") (pintype "passive"))
    )
    (net (code "208") (name "/OFF_MEM_DOUT(6)") (class "Default")
      (node (ref "ICGTRRP2") (pin "AP24") (pinfunction "OFF_MEM_DOUT[6]_AP24") (pintype "passive"))
    )
    (net (code "209") (name "/OFF_MEM_DOUT(7)") (class "Default")
      (node (ref "ICGTRRP2") (pin "AR25") (pinfunction "OFF_MEM_DOUT[7]_AR25") (pintype "passive"))
    )
    (net (code "210") (name "/OFF_MEM_DOUT(8)") (class "Default")
      (node (ref "ICGTRRP2") (pin "AN25") (pinfunction "OFF_MEM_DOUT[8]_AN25") (pintype "passive"))
    )
    (net (code "211") (name "/OFF_MEM_DOUT(9)") (class "Default")
      (node (ref "ICGTRRP2") (pin "AP26") (pinfunction "OFF_MEM_DOUT[9]_AP26") (pintype "passive"))
    )
    (net (code "212") (name "/OFF_MEM_DOUT(10)") (class "Default")
      (node (ref "ICGTRRP2") (pin "AR27") (pinfunction "OFF_MEM_DOUT[10]_AR27") (pintype "passive"))
    )
    (net (code "213") (name "/OFF_MEM_DOUT(11)") (class "Default")
      (node (ref "ICGTRRP2") (pin "AP28") (pinfunction "OFF_MEM_DOUT[11]_AP28") (pintype "passive"))
    )
    (net (code "214") (name "/OFF_MEM_DOUT(12)") (class "Default")
      (node (ref "ICGTRRP2") (pin "AN27") (pinfunction "OFF_MEM_DOUT[12]_AN27") (pintype "passive"))
    )
    (net (code "215") (name "/OFF_MEM_DOUT(13)") (class "Default")
      (node (ref "ICGTRRP2") (pin "AR29") (pinfunction "OFF_MEM_DOUT[13]_AR29") (pintype "passive"))
    )
    (net (code "216") (name "/OFF_MEM_DOUT(14)") (class "Default")
      (node (ref "ICGTRRP2") (pin "AR31") (pinfunction "OFF_MEM_DOUT[14]_AR31") (pintype "passive"))
    )
    (net (code "217") (name "/OFF_MEM_DOUT(15)") (class "Default")
      (node (ref "ICGTRRP2") (pin "AP30") (pinfunction "OFF_MEM_DOUT[15]_AP30") (pintype "passive"))
    )
    (net (code "218") (name "/OFF_MEM_WE") (class "Default")
      (node (ref "ICGTRRP2") (pin "AG33") (pinfunction "OFF_MEM_WE_AG33") (pintype "passive"))
    )
    (net (code "219") (name "/P") (class "Default")
      (node (ref "ICGTRRP2") (pin "W33") (pinfunction "P_W33") (pintype "passive"))
    )
    (net (code "220") (name "/PER_ADDR(0)") (class "Default")
      (node (ref "ICGTRRP2") (pin "AK8") (pinfunction "PER_ADDR[0]_AK8") (pintype "passive"))
    )
    (net (code "221") (name "/PER_ADDR(1)") (class "Default")
      (node (ref "ICGTRRP2") (pin "AL7") (pinfunction "PER_ADDR[1]_AL7") (pintype "passive"))
    )
    (net (code "222") (name "/PER_ADDR(2)") (class "Default")
      (node (ref "ICGTRRP2") (pin "AK10") (pinfunction "PER_ADDR[2]_AK10") (pintype "passive"))
    )
    (net (code "223") (name "/PER_ADDR(3)") (class "Default")
      (node (ref "ICGTRRP2") (pin "AJ11") (pinfunction "PER_ADDR[3]_AJ11") (pintype "passive"))
    )
    (net (code "224") (name "/PER_ADDR(4)") (class "Default")
      (node (ref "ICGTRRP2") (pin "AL9") (pinfunction "PER_ADDR[4]_AL9") (pintype "passive"))
    )
    (net (code "225") (name "/PER_ADDR(5)") (class "Default")
      (node (ref "ICGTRRP2") (pin "AM8") (pinfunction "PER_ADDR[5]_AM8") (pintype "passive"))
    )
    (net (code "226") (name "/PER_ADDR(6)") (class "Default")
      (node (ref "ICGTRRP2") (pin "AM10") (pinfunction "PER_ADDR[6]_AM10") (pintype "passive"))
    )
    (net (code "227") (name "/PER_ADDR(7)") (class "Default")
      (node (ref "ICGTRRP2") (pin "AL11") (pinfunction "PER_ADDR[7]_AL11") (pintype "passive"))
    )
    (net (code "228") (name "/PER_ADDR(8)") (class "Default")
      (node (ref "ICGTRRP2") (pin "AK12") (pinfunction "PER_ADDR[8]_AK12") (pintype "passive"))
    )
    (net (code "229") (name "/PER_ADDR(9)") (class "Default")
      (node (ref "ICGTRRP2") (pin "AM12") (pinfunction "PER_ADDR[9]_AM12") (pintype "passive"))
    )
    (net (code "230") (name "/PER_ADDR(10)") (class "Default")
      (node (ref "ICGTRRP2") (pin "AJ13") (pinfunction "PER_ADDR[10]_AJ13") (pintype "passive"))
    )
    (net (code "231") (name "/PER_ADDR(11)") (class "Default")
      (node (ref "ICGTRRP2") (pin "AL13") (pinfunction "PER_ADDR[11]_AL13") (pintype "passive"))
    )
    (net (code "232") (name "/PER_ADDR(12)") (class "Default")
      (node (ref "ICGTRRP2") (pin "AK14") (pinfunction "PER_ADDR[12]_AK14") (pintype "passive"))
    )
    (net (code "233") (name "/PER_ADDR(13)") (class "Default")
      (node (ref "ICGTRRP2") (pin "AM14") (pinfunction "PER_ADDR[13]_AM14") (pintype "passive"))
    )
    (net (code "234") (name "/PER_EN") (class "Default")
      (node (ref "ICGTRRP2") (pin "AN15") (pinfunction "PER_EN_AN15") (pintype "passive"))
    )
    (net (code "235") (name "/PER_WEN") (class "Default")
      (node (ref "ICGTRRP2") (pin "AP14") (pinfunction "PER_WEN_AP14") (pintype "passive"))
    )
    (net (code "236") (name "/PHI1_A") (class "Default")
      (node (ref "ICGTRRP2") (pin "N5") (pinfunction "PHI1_A_N5") (pintype "passive"))
    )
    (net (code "237") (name "/PHI1_B") (class "Default")
      (node (ref "ICGTRRP2") (pin "AC3") (pinfunction "PHI1_B_AC3") (pintype "passive"))
    )
    (net (code "238") (name "/PHI1_D") (class "Default")
      (node (ref "ICGTRRP2") (pin "K34") (pinfunction "PHI1_K34") (pintype "passive"))
    )
    (net (code "239") (name "/PHI2_A") (class "Default")
      (node (ref "ICGTRRP2") (pin "P6") (pinfunction "PHI2_A_P6") (pintype "passive"))
    )
    (net (code "240") (name "/PHI2_B") (class "Default")
      (node (ref "ICGTRRP2") (pin "AB2") (pinfunction "PHI2_B_AB2") (pintype "passive"))
    )
    (net (code "241") (name "/PHI2_D") (class "Default")
      (node (ref "ICGTRRP2") (pin "M34") (pinfunction "PHI2_M34") (pintype "passive"))
    )
    (net (code "242") (name "/PHI3_A") (class "Default")
      (node (ref "ICGTRRP2") (pin "N7") (pinfunction "PHI3_A_N7") (pintype "passive"))
    )
    (net (code "243") (name "/PHI3_D") (class "Default")
      (node (ref "ICGTRRP2") (pin "N33") (pinfunction "PHI3_N33") (pintype "passive"))
    )
    (net (code "244") (name "/REF1A") (class "Default")
      (node (ref "ICGTRRP2") (pin "D28") (pinfunction "REF1A_D28") (pintype "passive"))
    )
    (net (code "245") (name "/REF1B") (class "Default")
      (node (ref "ICGTRRP2") (pin "A29") (pinfunction "REF1B_A29") (pintype "passive"))
    )
    (net (code "246") (name "/REF1C") (class "Default")
      (node (ref "ICGTRRP2") (pin "C29") (pinfunction "REF1C_C29") (pintype "passive"))
    )
    (net (code "247") (name "/REF2A") (class "Default")
      (node (ref "ICGTRRP2") (pin "G11") (pinfunction "REF2A_G11") (pintype "passive"))
    )
    (net (code "248") (name "/REF2B") (class "Default")
      (node (ref "ICGTRRP2") (pin "A17") (pinfunction "REF2B_A17") (pintype "passive"))
    )
    (net (code "249") (name "/REF3A") (class "Default")
      (node (ref "ICGTRRP2") (pin "F24") (pinfunction "REF3A_F24") (pintype "passive"))
    )
    (net (code "250") (name "/REF3B") (class "Default")
      (node (ref "ICGTRRP2") (pin "A31") (pinfunction "REF3B_A31") (pintype "passive"))
    )
    (net (code "251") (name "/REF4A") (class "Default")
      (node (ref "ICGTRRP2") (pin "D10") (pinfunction "REF4A_D10") (pintype "passive"))
    )
    (net (code "252") (name "/REF4B") (class "Default")
      (node (ref "ICGTRRP2") (pin "C17") (pinfunction "REF4B_C17") (pintype "passive"))
    )
    (net (code "253") (name "/REF5A") (class "Default")
      (node (ref "ICGTRRP2") (pin "E21") (pinfunction "REF5A_E21") (pintype "passive"))
    )
    (net (code "254") (name "/REF5B") (class "Default")
      (node (ref "ICGTRRP2") (pin "B16") (pinfunction "REF5B_B16") (pintype "passive"))
    )
    (net (code "255") (name "/REF6A") (class "Default")
      (node (ref "ICGTRRP2") (pin "D14") (pinfunction "REF6A_D14") (pintype "passive"))
    )
    (net (code "256") (name "/REF6B") (class "Default")
      (node (ref "ICGTRRP2") (pin "G5") (pinfunction "REF6B_G5") (pintype "passive"))
    )
    (net (code "257") (name "/REF7A") (class "Default")
      (node (ref "ICGTRRP2") (pin "G19") (pinfunction "REF7A_G19") (pintype "passive"))
    )
    (net (code "258") (name "/REF7B") (class "Default")
      (node (ref "ICGTRRP2") (pin "A15") (pinfunction "REF7B_A15") (pintype "passive"))
    )
    (net (code "259") (name "/REF8A") (class "Default")
      (node (ref "ICGTRRP2") (pin "F16") (pinfunction "REF8A_F16") (pintype "passive"))
    )
    (net (code "260") (name "/REF8B") (class "Default")
      (node (ref "ICGTRRP2") (pin "H6") (pinfunction "REF8B_H6") (pintype "passive"))
    )
    (net (code "261") (name "/REF_DC") (class "Default")
      (node (ref "ICGTRRP2") (pin "R3") (pinfunction "REF_DC_R3") (pintype "passive"))
    )
    (net (code "262") (name "/RST") (class "Default")
      (node (ref "ICGTRRP2") (pin "AN17") (pinfunction "RST_AN17") (pintype "passive"))
    )
    (net (code "263") (name "/SAT0") (class "Default")
      (node (ref "ICGTRRP2") (pin "AA33") (pinfunction "SAT0_AA33") (pintype "passive"))
    )
    (net (code "264") (name "/SET_COUNTER_1") (class "Default")
      (node (ref "ICGTRRP2") (pin "V6") (pinfunction "SET_COUNTER_V6") (pintype "passive"))
    )
    (net (code "265") (name "/SET_COUNTER_2") (class "Default")
      (node (ref "ICGTRRP2") (pin "R35") (pinfunction "SET_COUNTER_R35") (pintype "passive"))
    )
    (net (code "266") (name "/SH1_WR0") (class "Default")
      (node (ref "ICGTRRP2") (pin "AA5") (pinfunction "SH1_WR0_AA5") (pintype "passive"))
    )
    (net (code "267") (name "/SH1_WR0_A") (class "Default")
      (node (ref "ICGTRRP2") (pin "G35") (pinfunction "Shift1_Write0_A_G35") (pintype "passive"))
    )
    (net (code "268") (name "/SH1_WR0_B") (class "Default")
      (node (ref "ICGTRRP2") (pin "J35") (pinfunction "Shift1_Write0_B_J35") (pintype "passive"))
    )
    (net (code "269") (name "/SPI_CLK_D") (class "Default")
      (node (ref "ICGTRRP2") (pin "V34") (pinfunction "SPI_CLK_V34") (pintype "passive"))
    )
    (net (code "270") (name "/SPI_DATA_D") (class "Default")
      (node (ref "ICGTRRP2") (pin "U35") (pinfunction "SPI_DATA_U35") (pintype "passive"))
    )
    (net (code "271") (name "/SPI_LOAD_D") (class "Default")
      (node (ref "ICGTRRP2") (pin "U33") (pinfunction "SPI_LOAD_U33") (pintype "passive"))
    )
    (net (code "272") (name "/STIM_CLK") (class "Default")
      (node (ref "ICGTRRP2") (pin "W5") (pinfunction "STIM_CLK_W5") (pintype "passive"))
    )
    (net (code "273") (name "/STIM_DATA_D") (class "Default")
      (node (ref "ICGTRRP2") (pin "E35") (pinfunction "STIM_DATA_E35") (pintype "passive"))
    )
    (net (code "274") (name "/STIM_GND_A") (class "Default")
      (node (ref "ICGTRRP2") (pin "R1") (pinfunction "STIM_GND_A_R1") (pintype "passive"))
    )
    (net (code "275") (name "/STIM_GND_B") (class "Default")
      (node (ref "ICGTRRP2") (pin "W1") (pinfunction "STIM_GND_B_W1") (pintype "passive"))
    )
    (net (code "276") (name "/STIM_GND_C") (class "Default")
      (node (ref "ICGTRRP2") (pin "U3") (pinfunction "STIM_GND_C_U3") (pintype "passive"))
    )
    (net (code "277") (name "/STIM_GND_D") (class "Default")
      (node (ref "ICGTRRP2") (pin "U31") (pinfunction "STIM_GND_U31") (pintype "passive"))
    )
    (net (code "278") (name "/STIM_IN") (class "Default")
      (node (ref "ICGTRRP2") (pin "AB6") (pinfunction "STIM_IN_AB6") (pintype "passive"))
    )
    (net (code "279") (name "/STIM_LOAD") (class "Default")
      (node (ref "ICGTRRP2") (pin "AB4") (pinfunction "STIM_LOAD_AB4") (pintype "passive"))
    )
    (net (code "280") (name "/STIM_LOAD_D") (class "Default")
      (node (ref "ICGTRRP2") (pin "F34") (pinfunction "STIM_LOAD_F34") (pintype "passive"))
    )
    (net (code "281") (name "/SYSTEM_DONE") (class "Default")
      (node (ref "ICGTRRP2") (pin "AP18") (pinfunction "SYSTEM_DONE_AP18") (pintype "passive"))
    )
    (net (code "282") (name "/TEST_MODE") (class "Default")
      (node (ref "ICGTRRP2") (pin "AD6") (pinfunction "TEST_MODE_AD6") (pintype "passive"))
    )
    (net (code "283") (name "/TEST_SE") (class "Default")
      (node (ref "ICGTRRP2") (pin "AD4") (pinfunction "TEST_SE_AD4") (pintype "passive"))
    )
    (net (code "284") (name "/TEST_SI1") (class "Default")
      (node (ref "ICGTRRP2") (pin "AC7") (pinfunction "TEST_SI1_AC7") (pintype "passive"))
    )
    (net (code "285") (name "/TEST_SI2") (class "Default")
      (node (ref "ICGTRRP2") (pin "AC5") (pinfunction "TEST_SI2_AC5") (pintype "passive"))
    )
    (net (code "286") (name "/TEST_SI3") (class "Default")
      (node (ref "ICGTRRP2") (pin "AH2") (pinfunction "TEST_SI3_AH2") (pintype "passive"))
    )
    (net (code "287") (name "/TEST_SO1") (class "Default")
      (node (ref "ICGTRRP2") (pin "AF2") (pinfunction "TEST_SO1_AF2") (pintype "passive"))
    )
    (net (code "288") (name "/TEST_SO2") (class "Default")
      (node (ref "ICGTRRP2") (pin "AE3") (pinfunction "TEST_SO2_AE3") (pintype "passive"))
    )
    (net (code "289") (name "/TEST_SO3") (class "Default")
      (node (ref "ICGTRRP2") (pin "AE1") (pinfunction "TEST_SO3_AE1") (pintype "passive"))
    )
    (net (code "290") (name "/VDD_D") (class "Default")
      (node (ref "ICGTRRP2") (pin "U29") (pinfunction "VDD_U29") (pintype "passive"))
    )
    (net (code "291") (name "/VDD_LOGIC") (class "Default")
      (node (ref "ICGTRRP2") (pin "AH34") (pinfunction "VDD_LOGIC_AH34") (pintype "passive"))
      (node (ref "ICGTRRP2") (pin "AJ1") (pinfunction "VDD_LOGIC_AJ1") (pintype "passive"))
      (node (ref "ICGTRRP2") (pin "AR15") (pinfunction "VDD_LOGIC_AR15") (pintype "passive"))
    )
    (net (code "292") (name "/VDD_MEMORY") (class "Default")
      (node (ref "ICGTRRP2") (pin "AA3") (pinfunction "VDD_MEMORY_AA3") (pintype "passive"))
      (node (ref "ICGTRRP2") (pin "W35") (pinfunction "VDD_MEMORY_W35") (pintype "passive"))
    )
    (net (code "293") (name "/VDD_PUMP_A") (class "Default")
      (node (ref "ICGTRRP2") (pin "T6") (pinfunction "VDD_PUMP_A_T6") (pintype "passive"))
    )
    (net (code "294") (name "/VDD_PUMP_B") (class "Default")
      (node (ref "ICGTRRP2") (pin "AD2") (pinfunction "VDD_PUMP_B_AD2") (pintype "passive"))
    )
    (net (code "295") (name "/VDD_PUMP_C") (class "Default")
      (node (ref "ICGTRRP2") (pin "L1") (pinfunction "VDD_PUMP_C_L1") (pintype "passive"))
    )
    (net (code "296") (name "/VDD_X") (class "Default")
      (node (ref "ICGTRRP2") (pin "Y6") (pinfunction "VDD_X_Y6") (pintype "passive"))
    )
    (net (code "297") (name "/VINN1") (class "Default")
      (node (ref "ICGTRRP2") (pin "W29") (pinfunction "VINN1_W29") (pintype "passive"))
    )
    (net (code "298") (name "/VINN2") (class "Default")
      (node (ref "ICGTRRP2") (pin "V32") (pinfunction "VINN2_V32") (pintype "passive"))
    )
    (net (code "299") (name "/VINP") (class "Default")
      (node (ref "ICGTRRP2") (pin "W31") (pinfunction "VINP_W31") (pintype "passive"))
    )
    (net (code "300") (name "/VREF1") (class "Default")
      (node (ref "ICGTRRP2") (pin "P32") (pinfunction "VREF1_P32") (pintype "passive"))
    )
    (net (code "301") (name "/VREF2") (class "Default")
      (node (ref "ICGTRRP2") (pin "L31") (pinfunction "VREF2_L31") (pintype "passive"))
    )
    (net (code "302") (name "/VREF_A") (class "Default")
      (node (ref "ICGTRRP2") (pin "T4") (pinfunction "VREF_A_T4") (pintype "passive"))
    )
    (net (code "303") (name "/VSS") (class "Default")
      (node (ref "ICGTRRP2") (pin "F28") (pinfunction "VSS_F28") (pintype "passive"))
      (node (ref "ICGTRRP2") (pin "T32") (pinfunction "VSS_T32") (pintype "passive"))
      (node (ref "ICGTRRP2") (pin "Y4") (pinfunction "VSS_Y4") (pintype "passive"))
    )
    (net (code "304") (name "/Vint") (class "Default")
      (node (ref "ICGTRRP2") (pin "J5") (pinfunction "Vint_J5") (pintype "passive"))
    )
    (net (code "305") (name "/Vint_D") (class "Default")
      (node (ref "ICGTRRP2") (pin "R31") (pinfunction "Vint_R31") (pintype "passive"))
    )
    (net (code "306") (name "/~{CL}K_D") (class "Default")
      (node (ref "ICGTRRP2") (pin "K30") (pinfunction "~{CLK}_K30") (pintype "passive"))
    )
    (net (code "307") (name "/~{D}") (class "Default")
      (node (ref "ICGTRRP2") (pin "L7") (pinfunction "~{D}_L7") (pintype "passive"))
    )
    (net (code "308") (name "/~{D}_buff1") (class "Default")
      (node (ref "ICGTRRP2") (pin "P30") (pinfunction "~{D}_buff1_P30") (pintype "passive"))
    )
    (net (code "309") (name "/~{D}_buff2") (class "Default")
      (node (ref "ICGTRRP2") (pin "N29") (pinfunction "~{D}_buff2_N29") (pintype "passive"))
    )
  )
)
